# RotaryPCB_v9.net
KiCad netlist of a schematic drawn in EAGLE
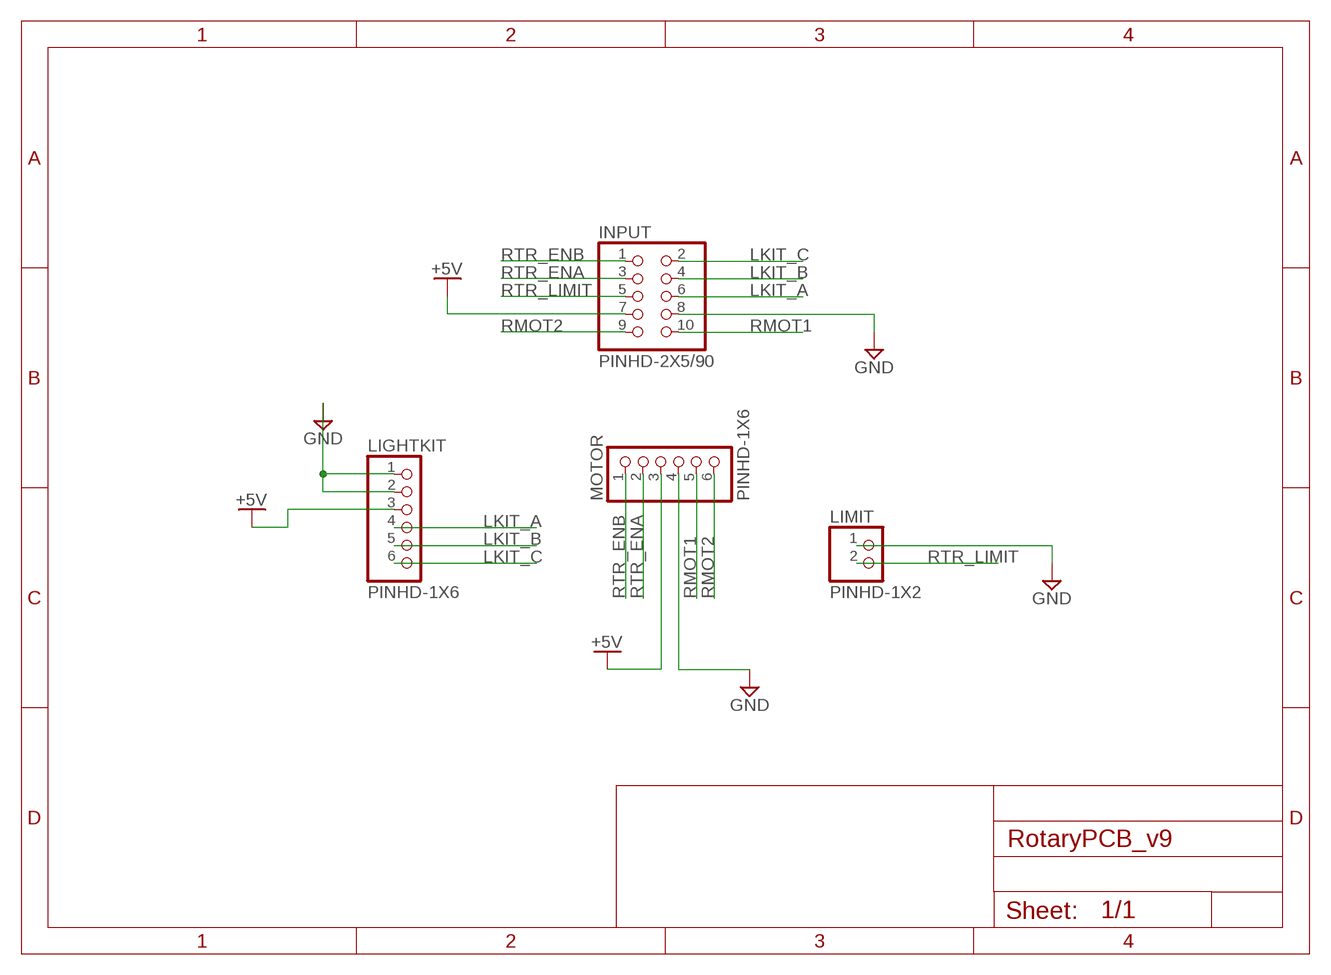
[diagram p0: schematic, sheet 1]

(export (version "E")
  (design (tool "Eeschema 10.0.6"))
  (components
    (comp (ref "INPUT")
      (value "PINHD-2X5/90")
      (footprint "eagle-import:2X05_90")
      (libsource (lib "eagle-import") (part "PINHD-2X5/90"))
    )
    (comp (ref "LIGHTKIT")
      (value "PINHD-1X6")
      (footprint "eagle-import:1X06")
      (libsource (lib "eagle-import") (part "PINHD-1X6"))
    )
    (comp (ref "LIMIT")
      (value "PINHD-1X2")
      (footprint "eagle-import:1X02")
      (libsource (lib "eagle-import") (part "PINHD-1X2"))
    )
    (comp (ref "MOTOR")
      (value "PINHD-1X6")
      (footprint "eagle-import:1X06")
      (libsource (lib "eagle-import") (part "PINHD-1X6"))
    )
  )
  (nets
    (net (code "1") (name "+5V") (class "Default")
      (node (ref "INPUT") (pin "7") (pinfunction "7_7") (pintype "passive"))
      (node (ref "LIGHTKIT") (pin "3") (pinfunction "3_3") (pintype "passive"))
      (node (ref "MOTOR") (pin "3") (pinfunction "3_3") (pintype "passive"))
    )
    (net (code "2") (name "/LKIT_A") (class "Default")
      (node (ref "INPUT") (pin "6") (pinfunction "6_6") (pintype "passive"))
      (node (ref "LIGHTKIT") (pin "4") (pinfunction "4_4") (pintype "passive"))
    )
    (net (code "3") (name "/LKIT_B") (class "Default")
      (node (ref "INPUT") (pin "4") (pinfunction "4_4") (pintype "passive"))
      (node (ref "LIGHTKIT") (pin "5") (pinfunction "5_5") (pintype "passive"))
    )
    (net (code "4") (name "/LKIT_C") (class "Default")
      (node (ref "INPUT") (pin "2") (pinfunction "2_2") (pintype "passive"))
      (node (ref "LIGHTKIT") (pin "6") (pinfunction "6_6") (pintype "passive"))
    )
    (net (code "5") (name "/RMOT1") (class "Default")
      (node (ref "INPUT") (pin "10") (pinfunction "10_10") (pintype "passive"))
      (node (ref "MOTOR") (pin "5") (pinfunction "5_5") (pintype "passive"))
    )
    (net (code "6") (name "/RMOT2") (class "Default")
      (node (ref "INPUT") (pin "9") (pinfunction "9_9") (pintype "passive"))
      (node (ref "MOTOR") (pin "6") (pinfunction "6_6") (pintype "passive"))
    )
    (net (code "7") (name "/RTR_ENA") (class "Default")
      (node (ref "INPUT") (pin "3") (pinfunction "3_3") (pintype "passive"))
      (node (ref "MOTOR") (pin "2") (pinfunction "2_2") (pintype "passive"))
    )
    (net (code "8") (name "/RTR_ENB") (class "Default")
      (node (ref "INPUT") (pin "1") (pinfunction "1_1") (pintype "passive"))
      (node (ref "MOTOR") (pin "1") (pinfunction "1_1") (pintype "passive"))
    )
    (net (code "9") (name "/RTR_LIMIT") (class "Default")
      (node (ref "INPUT") (pin "5") (pinfunction "5_5") (pintype "passive"))
      (node (ref "LIMIT") (pin "2") (pinfunction "2_2") (pintype "passive"))
    )
    (net (code "10") (name "GND") (class "Default")
      (node (ref "INPUT") (pin "8") (pinfunction "8_8") (pintype "passive"))
      (node (ref "LIGHTKIT") (pin "1") (pinfunction "1_1") (pintype "passive"))
      (node (ref "LIGHTKIT") (pin "2") (pinfunction "2_2") (pintype "passive"))
      (node (ref "LIMIT") (pin "1") (pinfunction "1_1") (pintype "passive"))
      (node (ref "MOTOR") (pin "4") (pinfunction "4_4") (pintype "passive"))
    )
  )
)
